# FT232RLschematic.net
KiCad netlist of a schematic drawn in Altium Designer
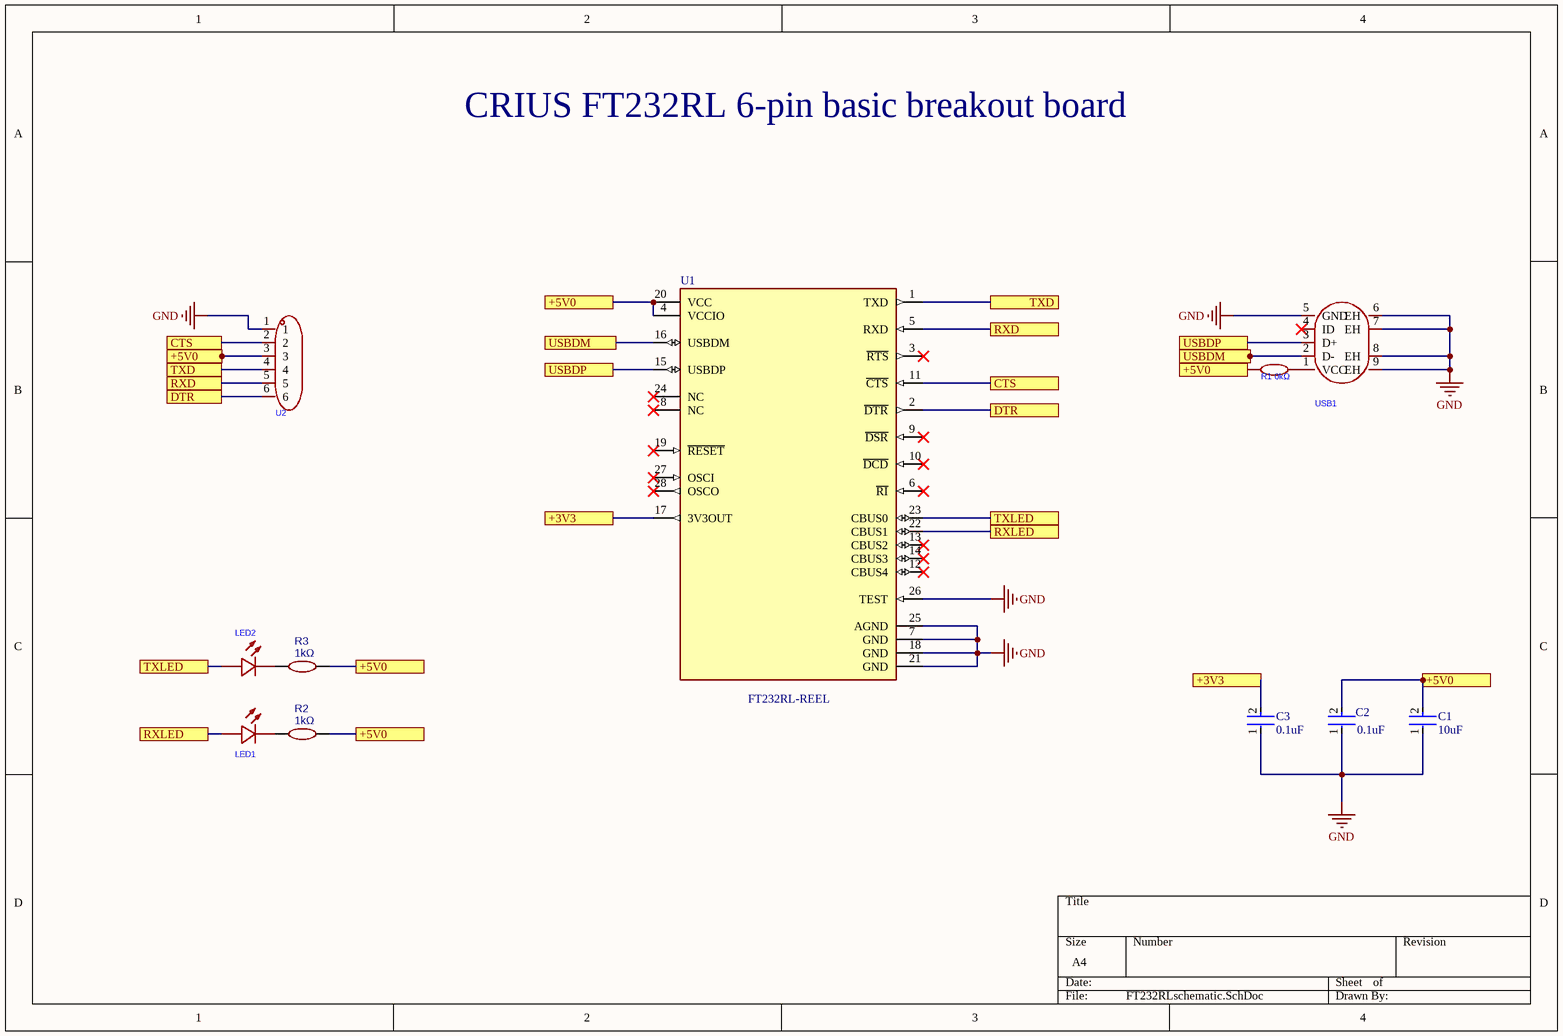
[diagram p0: FT232RLschematic.SchDoc]

(export (version "E")
  (design (tool "Eeschema 10.0.6"))
  (components
    (comp (ref "C1")
      (value "10uF")
      (footprint "FP-GRM15-MFG")
      (description "CAP CER 0.1UF 16V X7R 0402")
      (fields (field (name "MANUFACTURER PART NUMBER") "GRM155R71C104KA88D") (field (name "TOLERANCE") "10%"))
      (libsource (lib "Altium Content Vault") (part "236180d848d6139a670b325ea6854c9"))
    )
    (comp (ref "C2")
      (value "0.1uF")
      (footprint "FP-GRM15-MFG")
      (description "CAP CER 0.1UF 16V X7R 0402")
      (fields (field (name "MANUFACTURER PART NUMBER") "GRM155R71C104KA88D") (field (name "TOLERANCE") "10%"))
      (libsource (lib "Altium Content Vault") (part "236180d848d6139a670b325ea6854c9"))
    )
    (comp (ref "C3")
      (value "0.1uF")
      (footprint "FP-GRM15-MFG")
      (description "CAP CER 0.1UF 16V X7R 0402")
      (fields (field (name "MANUFACTURER PART NUMBER") "GRM155R71C104KA88D") (field (name "TOLERANCE") "10%"))
      (libsource (lib "Altium Content Vault") (part "236180d848d6139a670b325ea6854c9"))
    )
    (comp (ref "LED1")
      (value "YLED0603R")
      (footprint "LED0603-FD")
      (fields (field (name "MANUFACTURER") "YONGYUTAI(永裕泰)"))
      (libsource (lib "altium-import") (part "root_0_YLED0603R_"))
    )
    (comp (ref "LED2")
      (value "YLED0603R")
      (footprint "LED0603-FD")
      (fields (field (name "MANUFACTURER") "YONGYUTAI(永裕泰)"))
      (libsource (lib "altium-import") (part "root_0_YLED0603R_"))
    )
    (comp (ref "R1")
      (value "0kΩ")
      (footprint "R0805")
      (fields
        (field (name "MANUFACTURER") "YAGEO(国巨)")
        (field (name "MANUFACTURER PART") "RC0805FR-0710KL")
        (field (name "TOLERANCE") "±1%")
      )
      (libsource (lib "altium-import") (part "root_0_RC0805FR-0710KL_"))
    )
    (comp (ref "R2")
      (value "1kΩ")
      (footprint "R0603")
      (fields (field (name "MANUFACTURER PART") "RC0603FR-071KL") (field (name "MANUFACTURER") "YAGEO(国巨)"))
      (libsource (lib "altium-import") (part "root_0_1kΩ_"))
    )
    (comp (ref "R3")
      (value "1kΩ")
      (footprint "R0603")
      (fields (field (name "MANUFACTURER PART") "RC0603FR-071KL") (field (name "MANUFACTURER") "YAGEO(国巨)"))
      (libsource (lib "altium-import") (part "root_0_1kΩ_"))
    )
    (comp (ref "U1")
      (value "FT232RL-REEL")
      (footprint "FP-SSOP-28-MFG")
      (description "IC USB FS SERIAL UART 28-SSOP")
      (fields (field (name "VOLTAGE") "5V"))
      (libsource (lib "Altium Content Vault") (part "fa727c664f4d88ca0f1b580aa0dd901"))
    )
    (comp (ref "U2")
      (value "HB-PH3-25416PB2GOP")
      (footprint "HDR-TH_6P-P2.54-V-M")
      (fields (field (name "MANUFACTURER") "HANBO(汉博)"))
      (libsource (lib "altium-import") (part "root_0_HB-PH3-25416PB2GOP_"))
    )
    (comp (ref "USB1")
      (value "KH-MINI-SMT-5P-Cu")
      (footprint "MINI-USB-SMD_KH-MINI-SMT-5P-CU")
      (fields (field (name "MANUFACTURER") "kinghelm(金航标)"))
      (libsource (lib "altium-import") (part "root_2_KH-MINI-SMT-5P-Cu_"))
    )
  )
  (nets
    (net (code "1") (name "/+3V3") (class "Default")
      (node (ref "C3") (pin "2") (pinfunction "2_2") (pintype "passive"))
      (node (ref "U1") (pin "17") (pinfunction "3V3OUT_17") (pintype "output"))
    )
    (net (code "2") (name "/+5V0") (class "Default")
      (node (ref "C1") (pin "2") (pinfunction "2_2") (pintype "passive"))
      (node (ref "C2") (pin "2") (pinfunction "2_2") (pintype "passive"))
      (node (ref "R1") (pin "1") (pinfunction "1_1") (pintype "passive"))
      (node (ref "R2") (pin "2") (pinfunction "2_2") (pintype "passive"))
      (node (ref "R3") (pin "2") (pinfunction "2_2") (pintype "passive"))
      (node (ref "U1") (pin "20") (pinfunction "VCC_20") (pintype "power_in"))
      (node (ref "U1") (pin "4") (pinfunction "VCCIO_4") (pintype "power_in"))
      (node (ref "U2") (pin "3") (pinfunction "3_3") (pintype "passive"))
    )
    (net (code "3") (name "/CTS") (class "Default")
      (node (ref "U1") (pin "11") (pinfunction "~{CTS}_11") (pintype "input"))
      (node (ref "U2") (pin "2") (pinfunction "2_2") (pintype "passive"))
    )
    (net (code "4") (name "/DTR") (class "Default")
      (node (ref "U1") (pin "2") (pinfunction "~{DTR}_2") (pintype "output"))
      (node (ref "U2") (pin "6") (pinfunction "6_6") (pintype "passive"))
    )
    (net (code "5") (name "/RXD") (class "Default")
      (node (ref "U1") (pin "5") (pinfunction "RXD_5") (pintype "input"))
      (node (ref "U2") (pin "5") (pinfunction "5_5") (pintype "passive"))
    )
    (net (code "6") (name "/RXLED") (class "Default")
      (node (ref "LED1") (pin "1") (pinfunction "+_1") (pintype "passive"))
      (node (ref "U1") (pin "22") (pinfunction "CBUS1_22") (pintype "bidirectional"))
    )
    (net (code "7") (name "/TXD") (class "Default")
      (node (ref "U1") (pin "1") (pinfunction "TXD_1") (pintype "output"))
      (node (ref "U2") (pin "4") (pinfunction "4_4") (pintype "passive"))
    )
    (net (code "8") (name "/TXLED") (class "Default")
      (node (ref "LED2") (pin "1") (pinfunction "+_1") (pintype "passive"))
      (node (ref "U1") (pin "23") (pinfunction "CBUS0_23") (pintype "bidirectional"))
    )
    (net (code "9") (name "/USBDM") (class "Default")
      (node (ref "U1") (pin "16") (pinfunction "USBDM_16") (pintype "bidirectional"))
      (node (ref "USB1") (pin "2") (pinfunction "D-_2") (pintype "passive"))
    )
    (net (code "10") (name "/USBDP") (class "Default")
      (node (ref "U1") (pin "15") (pinfunction "USBDP_15") (pintype "bidirectional"))
      (node (ref "USB1") (pin "3") (pinfunction "D+_3") (pintype "passive"))
    )
    (net (code "11") (name "GND") (class "Default")
      (node (ref "C1") (pin "1") (pinfunction "1_1") (pintype "passive"))
      (node (ref "C2") (pin "1") (pinfunction "1_1") (pintype "passive"))
      (node (ref "C3") (pin "1") (pinfunction "1_1") (pintype "passive"))
      (node (ref "U1") (pin "18") (pinfunction "GND_18") (pintype "power_in"))
      (node (ref "U1") (pin "21") (pinfunction "GND_21") (pintype "power_in"))
      (node (ref "U1") (pin "25") (pinfunction "AGND_25") (pintype "power_in"))
      (node (ref "U1") (pin "26") (pinfunction "TEST_26") (pintype "input"))
      (node (ref "U1") (pin "7") (pinfunction "GND_7") (pintype "power_in"))
      (node (ref "U2") (pin "1") (pinfunction "1_1") (pintype "passive"))
      (node (ref "USB1") (pin "5") (pinfunction "GND_5") (pintype "passive"))
      (node (ref "USB1") (pin "6") (pinfunction "EH_6") (pintype "passive"))
      (node (ref "USB1") (pin "7") (pinfunction "EH_7") (pintype "passive"))
      (node (ref "USB1") (pin "8") (pinfunction "EH_8") (pintype "passive"))
      (node (ref "USB1") (pin "9") (pinfunction "EH_9") (pintype "passive"))
    )
    (net (code "12") (name "Net-(LED1--)") (class "Default")
      (node (ref "LED1") (pin "2") (pinfunction "-_2") (pintype "passive"))
      (node (ref "R2") (pin "1") (pinfunction "1_1") (pintype "passive"))
    )
    (net (code "13") (name "Net-(LED2--)") (class "Default")
      (node (ref "LED2") (pin "2") (pinfunction "-_2") (pintype "passive"))
      (node (ref "R3") (pin "1") (pinfunction "1_1") (pintype "passive"))
    )
    (net (code "14") (name "Net-(USB1-VCC)") (class "Default")
      (node (ref "R1") (pin "2") (pinfunction "2_2") (pintype "passive"))
      (node (ref "USB1") (pin "1") (pinfunction "VCC_1") (pintype "passive"))
    )
    (net (code "15") (name "unconnected-(U1-CBUS2-Pad13)") (class "Default")
      (node (ref "U1") (pin "13") (pinfunction "CBUS2_13") (pintype "bidirectional+no_connect"))
    )
    (net (code "16") (name "unconnected-(U1-CBUS3-Pad14)") (class "Default")
      (node (ref "U1") (pin "14") (pinfunction "CBUS3_14") (pintype "bidirectional+no_connect"))
    )
    (net (code "17") (name "unconnected-(U1-CBUS4-Pad12)") (class "Default")
      (node (ref "U1") (pin "12") (pinfunction "CBUS4_12") (pintype "bidirectional+no_connect"))
    )
    (net (code "18") (name "unconnected-(U1-NC-Pad8)") (class "Default")
      (node (ref "U1") (pin "8") (pinfunction "NC_8") (pintype "passive+no_connect"))
    )
    (net (code "19") (name "unconnected-(U1-NC-Pad24)") (class "Default")
      (node (ref "U1") (pin "24") (pinfunction "NC_24") (pintype "passive+no_connect"))
    )
    (net (code "20") (name "unconnected-(U1-OSCI-Pad27)") (class "Default")
      (node (ref "U1") (pin "27") (pinfunction "OSCI_27") (pintype "input+no_connect"))
    )
    (net (code "21") (name "unconnected-(U1-OSCO-Pad28)") (class "Default")
      (node (ref "U1") (pin "28") (pinfunction "OSCO_28") (pintype "output+no_connect"))
    )
    (net (code "22") (name "unconnected-(U1-~{DCD}-Pad10)") (class "Default")
      (node (ref "U1") (pin "10") (pinfunction "~{DCD}_10") (pintype "input+no_connect"))
    )
    (net (code "23") (name "unconnected-(U1-~{DSR}-Pad9)") (class "Default")
      (node (ref "U1") (pin "9") (pinfunction "~{DSR}_9") (pintype "input+no_connect"))
    )
    (net (code "24") (name "unconnected-(U1-~{RESET}-Pad19)") (class "Default")
      (node (ref "U1") (pin "19") (pinfunction "~{RESET}_19") (pintype "input+no_connect"))
    )
    (net (code "25") (name "unconnected-(U1-~{RI}-Pad6)") (class "Default")
      (node (ref "U1") (pin "6") (pinfunction "~{RI}_6") (pintype "input+no_connect"))
    )
    (net (code "26") (name "unconnected-(U1-~{RTS}-Pad3)") (class "Default")
      (node (ref "U1") (pin "3") (pinfunction "~{RTS}_3") (pintype "output+no_connect"))
    )
    (net (code "27") (name "unconnected-(USB1-ID-Pad4)") (class "Default")
      (node (ref "USB1") (pin "4") (pinfunction "ID_4") (pintype "passive+no_connect"))
    )
  )
)
